# STM32.net
KiCad netlist of a schematic drawn in Altium Designer
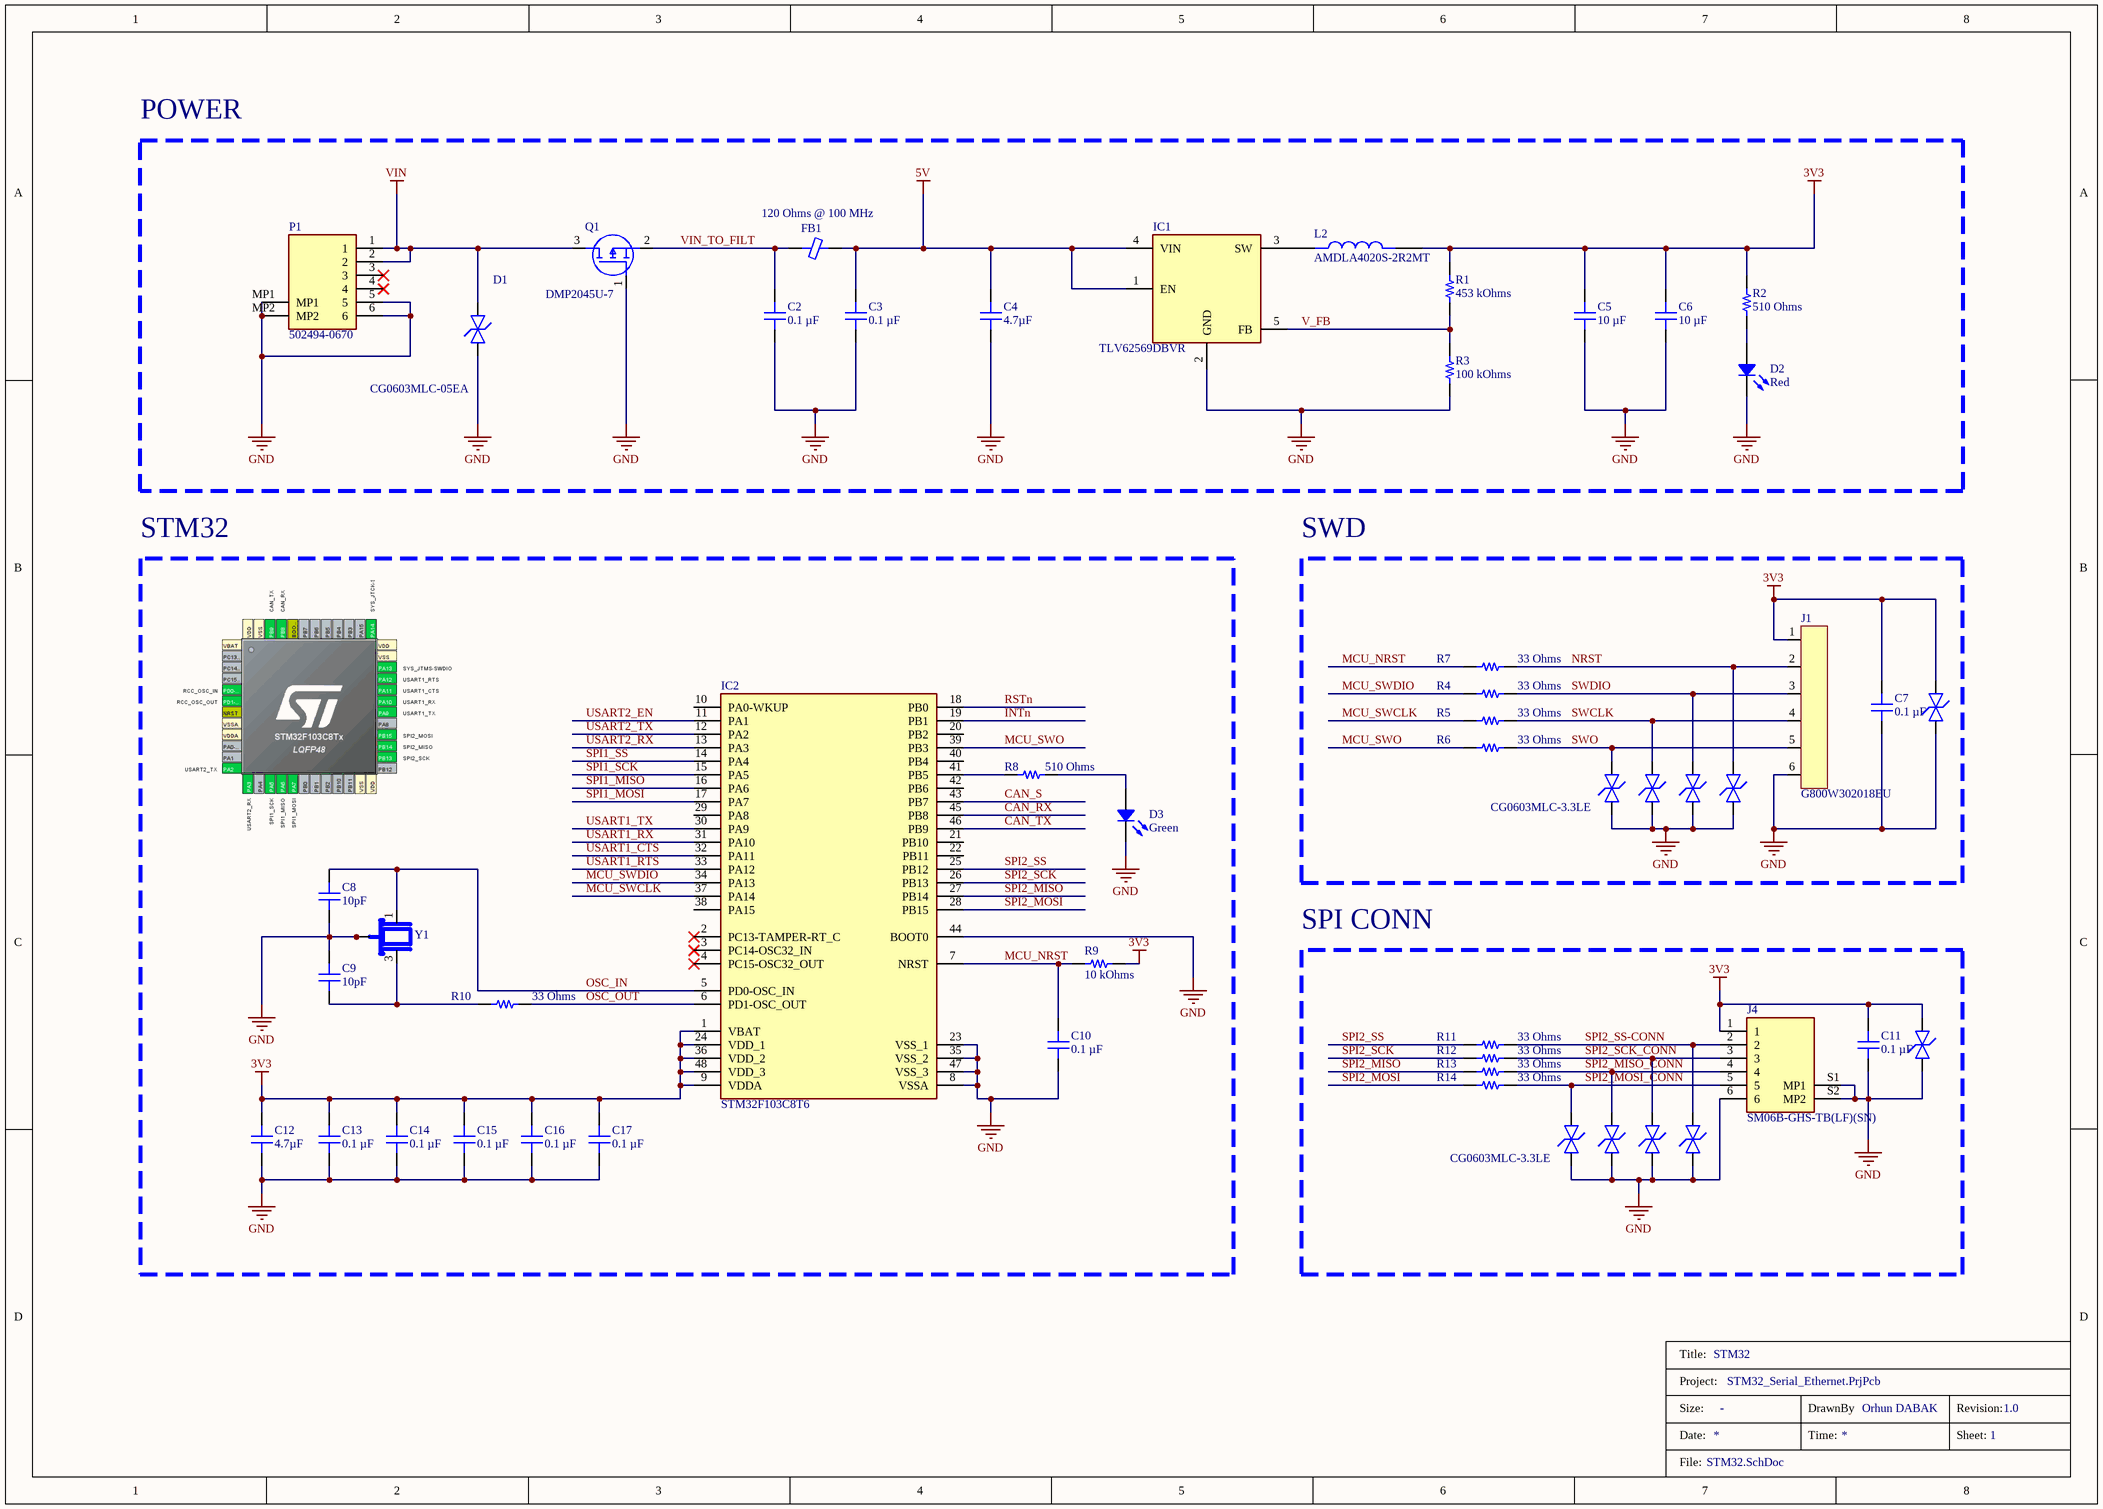
[diagram p0: STM32.SchDoc]

(export (version "E")
  (design (tool "Eeschema 10.0.6"))
  (components
    (comp (ref "C2")
      (value "0.1 µF")
      (footprint "CAP 0603_1608")
      (description "CAP CER 0.1UF 16V X7R 0603")
      (fields (field (name "PART NUMBER") "CS0603KRX7R7BB104") (field (name "MANUFACTURER") "Yageo"))
      (libsource (lib "Celestial Altium Library - altium_library") (part "Capacitor"))
    )
    (comp (ref "C3")
      (value "0.1 µF")
      (footprint "CAP 0603_1608")
      (description "CAP CER 0.1UF 16V X7R 0603")
      (fields (field (name "PART NUMBER") "CS0603KRX7R7BB104") (field (name "MANUFACTURER") "Yageo"))
      (libsource (lib "Celestial Altium Library - altium_library") (part "Capacitor"))
    )
    (comp (ref "C4")
      (value "4.7µF")
      (footprint "CAP 0805_2012")
      (description "CAP CER 4.7UF 16V X7R 0805")
      (fields (field (name "PART NUMBER") "0805YC475MAT2A") (field (name "MANUFACTURER") "AVX Corporation"))
      (libsource (lib "Celestial Altium Library - altium_library") (part "Capacitor"))
    )
    (comp (ref "C5")
      (value "10 µF")
      (footprint "CAP 0805_2012")
      (description "CAP CER 10UF 16V X6S 0805")
      (fields
        (field (name "PART NUMBER") "C2012X6S1C106K125AC")
        (field (name "MANUFACTURER") "TDK Corporation")
      )
      (libsource (lib "Celestial Altium Library - altium_library") (part "Capacitor"))
    )
    (comp (ref "C6")
      (value "10 µF")
      (footprint "CAP 0805_2012")
      (description "CAP CER 10UF 16V X6S 0805")
      (fields
        (field (name "PART NUMBER") "C2012X6S1C106K125AC")
        (field (name "MANUFACTURER") "TDK Corporation")
      )
      (libsource (lib "Celestial Altium Library - altium_library") (part "Capacitor"))
    )
    (comp (ref "C7")
      (value "0.1 µF")
      (footprint "CAP 0603_1608")
      (description "CAP CER 0.1UF 16V X7R 0603")
      (fields (field (name "PART NUMBER") "CS0603KRX7R7BB104") (field (name "MANUFACTURER") "Yageo"))
      (libsource (lib "Celestial Altium Library - altium_library") (part "Capacitor"))
    )
    (comp (ref "C8")
      (value "10pF")
      (footprint "CAP 0603_1608")
      (description "CAP CER 10PF 50V NP0 0603")
      (fields (field (name "PART NUMBER") "06035A100J4T2A") (field (name "MANUFACTURER") "AVX Corporation"))
      (libsource (lib "Celestial Altium Library - altium_library") (part "Capacitor"))
    )
    (comp (ref "C9")
      (value "10pF")
      (footprint "CAP 0603_1608")
      (description "CAP CER 10PF 50V NP0 0603")
      (fields (field (name "PART NUMBER") "06035A100J4T2A") (field (name "MANUFACTURER") "AVX Corporation"))
      (libsource (lib "Celestial Altium Library - altium_library") (part "Capacitor"))
    )
    (comp (ref "C10")
      (value "0.1 µF")
      (footprint "CAP 0603_1608")
      (description "CAP CER 0.1UF 16V X7R 0603")
      (fields (field (name "PART NUMBER") "CS0603KRX7R7BB104") (field (name "MANUFACTURER") "Yageo"))
      (libsource (lib "Celestial Altium Library - altium_library") (part "Capacitor"))
    )
    (comp (ref "C11")
      (value "0.1 µF")
      (footprint "CAP 0603_1608")
      (description "CAP CER 0.1UF 16V X7R 0603")
      (fields (field (name "PART NUMBER") "CS0603KRX7R7BB104") (field (name "MANUFACTURER") "Yageo"))
      (libsource (lib "Celestial Altium Library - altium_library") (part "Capacitor"))
    )
    (comp (ref "C12")
      (value "4.7µF")
      (footprint "CAP 0805_2012")
      (description "CAP CER 4.7UF 16V X7R 0805")
      (fields (field (name "PART NUMBER") "0805YC475MAT2A") (field (name "MANUFACTURER") "AVX Corporation"))
      (libsource (lib "Celestial Altium Library - altium_library") (part "Capacitor"))
    )
    (comp (ref "C13")
      (value "0.1 µF")
      (footprint "CAP 0603_1608")
      (description "CAP CER 0.1UF 16V X7R 0603")
      (fields (field (name "PART NUMBER") "CS0603KRX7R7BB104") (field (name "MANUFACTURER") "Yageo"))
      (libsource (lib "Celestial Altium Library - altium_library") (part "Capacitor"))
    )
    (comp (ref "C14")
      (value "0.1 µF")
      (footprint "CAP 0603_1608")
      (description "CAP CER 0.1UF 16V X7R 0603")
      (fields (field (name "PART NUMBER") "CS0603KRX7R7BB104") (field (name "MANUFACTURER") "Yageo"))
      (libsource (lib "Celestial Altium Library - altium_library") (part "Capacitor"))
    )
    (comp (ref "C15")
      (value "0.1 µF")
      (footprint "CAP 0603_1608")
      (description "CAP CER 0.1UF 16V X7R 0603")
      (fields (field (name "PART NUMBER") "CS0603KRX7R7BB104") (field (name "MANUFACTURER") "Yageo"))
      (libsource (lib "Celestial Altium Library - altium_library") (part "Capacitor"))
    )
    (comp (ref "C16")
      (value "0.1 µF")
      (footprint "CAP 0603_1608")
      (description "CAP CER 0.1UF 16V X7R 0603")
      (fields (field (name "PART NUMBER") "CS0603KRX7R7BB104") (field (name "MANUFACTURER") "Yageo"))
      (libsource (lib "Celestial Altium Library - altium_library") (part "Capacitor"))
    )
    (comp (ref "C17")
      (value "0.1 µF")
      (footprint "CAP 0603_1608")
      (description "CAP CER 0.1UF 16V X7R 0603")
      (fields (field (name "PART NUMBER") "CS0603KRX7R7BB104") (field (name "MANUFACTURER") "Yageo"))
      (libsource (lib "Celestial Altium Library - altium_library") (part "Capacitor"))
    )
    (comp (ref "D1")
      (value "CG0603MLC-05EA")
      (footprint "SamacSys:DIONC1608X55N")
      (description "TVS Diode (Bi-directional)")
      (libsource (lib "SamacSys") (part "CG0603MLC-05EA"))
    )
    (comp (ref "D2")
      (value "Red")
      (footprint "LED 0603_1608 RED")
      (description "LED RED CLEAR CHIP SMD")
      (fields (field (name "PART NUMBER") "LTST-C193KRKT-2A") (field (name "MANUFACTURER") "Lite-On Inc."))
      (libsource (lib "Celestial Altium Library - altium_library") (part "LED"))
    )
    (comp (ref "D3")
      (value "Green")
      (footprint "LED 0603_1608 GREEN")
      (description "LED SM 0603 3V -/1000/-MCD GREEN")
      (fields
        (field (name "PART NUMBER") "LSM0603453V")
        (field (name "MANUFACTURER") "Visual Communications Company - VCC")
      )
      (libsource (lib "Celestial Altium Library - altium_library") (part "LED"))
    )
    (comp (ref "FB1")
      (value "120 Ohms @ 100 MHz")
      (footprint "FER 0603_1608")
      (description "FERRITE BEAD 120 OHM 0603 1LN")
      (fields (field (name "PART NUMBER") "742792625") (field (name "MANUFACTURER") "Würth Elektronik"))
      (libsource (lib "Celestial Altium Library - altium_library") (part "Ferrite Chip"))
    )
    (comp (ref "IC1")
      (value "TLV62569DBVR")
      (footprint "SamacSys:SOT95P280X145-5N")
      (description "Integrated Circuit")
      (fields (field (name "MOUSER PART NUMBER") "595-TLV62569DBVR"))
      (libsource (lib "SamacSys") (part "TLV62569DBVR"))
    )
    (comp (ref "IC2")
      (value "STM32F103C8T6")
      (footprint "SamacSys:QFP50P900X900X160-48N")
      (description "Integrated Circuit")
      (fields
        (field (name "MANUFACTURER_PART_NUMBER") "stm32f103c8t6")
        (field (name "MOUSER PART NUMBER") "511-STM32F103C8T6")
      )
      (libsource (lib "SamacSys") (part "STM32F103C8T6"))
    )
    (comp (ref "J1")
      (value "G800W302018EU")
      (footprint "G800W302018EU")
      (description "Pin Header 6 Position 2.54mm Pitch")
      (fields (field (name "MANUFACTURER") "Amphenol"))
      (libsource (lib "Schematic-Lib-PhilsLab") (part "G800W302018EU"))
    )
    (comp (ref "J4")
      (value "SM06B-GHS-TB(LF)(SN)")
      (footprint "SnapEDApcb:JST_SM06B-GHS-TB(LF)(SN)")
      (fields (field (name "MP") "SM06B-GHS-TB_LF__SN_") (field (name "MF") "JST Sales"))
      (libsource (lib "SnapEDAsch") (part "SM06B-GHS-TB(LF)(SN)"))
    )
    (comp (ref "L2")
      (value "AMDLA4020S-2R2MT")
      (footprint "IND_AMDLA4020S-2R2MT")
      (description "Power Inductor (SMD), 2.2 uH, Â± 20%, 4.5 A, Shielded, 6 A, 4.4mm x 4mm x 1.8mm")
      (fields (field (name "MF") "Abracon Corporation"))
      (libsource (lib "AMDLA4020S-2R2MT") (part "AMDLA4020S-2R2MT"))
    )
    (comp (ref "P1")
      (value "502494-0670")
      (footprint "MOLEX_502494-0670:MOLEX_502494-0670")
      (description "2.00mm Pitch CLIK-Mateâ„¢ Wire-to-Board PCB Receptacle, Single Row, Right Angle, 6 Circuits")
      (libsource (lib "502494-0670") (part "502494-0670"))
    )
    (comp (ref "Q1")
      (value "DMP2045U-7")
      (footprint "SamacSys:SOT96P240X110-3N")
      (description "MOSFET (P-Channel)")
      (fields (field (name "MOUSER PART NUMBER") "621-DMP2045U-7"))
      (libsource (lib "SamacSys") (part "DMP2045U-7"))
    )
    (comp (ref "R1")
      (value "453 kOhms")
      (footprint "RES 0603_1608")
      (description "RES SMD 453 KOHM 1% 0.3W 0603")
      (fields (field (name "PART NUMBER") "SDR03EZPF4533") (field (name "MANUFACTURER") "Rohm Semiconductor"))
      (libsource (lib "Celestial Altium Library - altium_library") (part "Resistor"))
    )
    (comp (ref "R2")
      (value "510 Ohms")
      (footprint "RES 0603_1608")
      (description "RES 510 OHM 5% 1/10W 0603")
      (fields
        (field (name "PART NUMBER") "RMCF0603JT510R")
        (field (name "MANUFACTURER") "Stackpole Electronics Inc")
      )
      (libsource (lib "Celestial Altium Library - altium_library") (part "Resistor"))
    )
    (comp (ref "R3")
      (value "100 kOhms")
      (footprint "RES 0603_1608")
      (description "RES SMD 100K OHM 1% 1/10W 0603")
      (fields (field (name "PART NUMBER") "RT0603FRE07100KL") (field (name "MANUFACTURER") "Yageo"))
      (libsource (lib "Celestial Altium Library - altium_library") (part "Resistor"))
    )
    (comp (ref "R4")
      (value "33 Ohms")
      (footprint "RES 0603_1608")
      (description "RES 33 OHM 5% 1/10W 0603")
      (fields
        (field (name "PART NUMBER") "RMCF0603JT33R0")
        (field (name "MANUFACTURER") "Stackpole Electronics Inc")
      )
      (libsource (lib "Celestial Altium Library - altium_library") (part "Resistor"))
    )
    (comp (ref "R5")
      (value "33 Ohms")
      (footprint "RES 0603_1608")
      (description "RES 33 OHM 5% 1/10W 0603")
      (fields
        (field (name "PART NUMBER") "RMCF0603JT33R0")
        (field (name "MANUFACTURER") "Stackpole Electronics Inc")
      )
      (libsource (lib "Celestial Altium Library - altium_library") (part "Resistor"))
    )
    (comp (ref "R6")
      (value "33 Ohms")
      (footprint "RES 0603_1608")
      (description "RES 33 OHM 5% 1/10W 0603")
      (fields
        (field (name "PART NUMBER") "RMCF0603JT33R0")
        (field (name "MANUFACTURER") "Stackpole Electronics Inc")
      )
      (libsource (lib "Celestial Altium Library - altium_library") (part "Resistor"))
    )
    (comp (ref "R7")
      (value "33 Ohms")
      (footprint "RES 0603_1608")
      (description "RES 33 OHM 5% 1/10W 0603")
      (fields
        (field (name "PART NUMBER") "RMCF0603JT33R0")
        (field (name "MANUFACTURER") "Stackpole Electronics Inc")
      )
      (libsource (lib "Celestial Altium Library - altium_library") (part "Resistor"))
    )
    (comp (ref "R8")
      (value "510 Ohms")
      (footprint "RES 0603_1608")
      (description "RES 510 OHM 5% 1/10W 0603")
      (fields
        (field (name "PART NUMBER") "RMCF0603JT510R")
        (field (name "MANUFACTURER") "Stackpole Electronics Inc")
      )
      (libsource (lib "Celestial Altium Library - altium_library") (part "Resistor"))
    )
    (comp (ref "R9")
      (value "10 kOhms")
      (footprint "RES 0603_1608")
      (description "RES SMD 10K OHM 5% 1/10W 0603")
      (fields (field (name "PART NUMBER") "CRCW060310K0JNEA") (field (name "MANUFACTURER") "Vishay Dale"))
      (libsource (lib "Celestial Altium Library - altium_library") (part "Resistor"))
    )
    (comp (ref "R10")
      (value "33 Ohms")
      (footprint "RES 0603_1608")
      (description "RES 33 OHM 5% 1/10W 0603")
      (fields
        (field (name "PART NUMBER") "RMCF0603JT33R0")
        (field (name "MANUFACTURER") "Stackpole Electronics Inc")
      )
      (libsource (lib "Celestial Altium Library - altium_library") (part "Resistor"))
    )
    (comp (ref "R11")
      (value "33 Ohms")
      (footprint "RES 0603_1608")
      (description "RES 33 OHM 5% 1/10W 0603")
      (fields
        (field (name "PART NUMBER") "RMCF0603JT33R0")
        (field (name "MANUFACTURER") "Stackpole Electronics Inc")
      )
      (libsource (lib "Celestial Altium Library - altium_library") (part "Resistor"))
    )
    (comp (ref "R12")
      (value "33 Ohms")
      (footprint "RES 0603_1608")
      (description "RES 33 OHM 5% 1/10W 0603")
      (fields
        (field (name "PART NUMBER") "RMCF0603JT33R0")
        (field (name "MANUFACTURER") "Stackpole Electronics Inc")
      )
      (libsource (lib "Celestial Altium Library - altium_library") (part "Resistor"))
    )
    (comp (ref "R13")
      (value "33 Ohms")
      (footprint "RES 0603_1608")
      (description "RES 33 OHM 5% 1/10W 0603")
      (fields
        (field (name "PART NUMBER") "RMCF0603JT33R0")
        (field (name "MANUFACTURER") "Stackpole Electronics Inc")
      )
      (libsource (lib "Celestial Altium Library - altium_library") (part "Resistor"))
    )
    (comp (ref "R14")
      (value "33 Ohms")
      (footprint "RES 0603_1608")
      (description "RES 33 OHM 5% 1/10W 0603")
      (fields
        (field (name "PART NUMBER") "RMCF0603JT33R0")
        (field (name "MANUFACTURER") "Stackpole Electronics Inc")
      )
      (libsource (lib "Celestial Altium Library - altium_library") (part "Resistor"))
    )
    (comp (ref "RV1")
      (value "CG0603MLC-3.3LE")
      (footprint "SamacSys:VARC1608X55N")
      (description "Varistor")
      (fields (field (name "MOUSER PART NUMBER") "652-CG0603MLC-3.3LE"))
      (libsource (lib "SamacSys") (part "CG0603MLC-3.3LE"))
    )
    (comp (ref "RV2")
      (value "CG0603MLC-3.3LE")
      (footprint "SamacSys:VARC1608X55N")
      (description "Varistor")
      (fields (field (name "MOUSER PART NUMBER") "652-CG0603MLC-3.3LE"))
      (libsource (lib "SamacSys") (part "CG0603MLC-3.3LE"))
    )
    (comp (ref "RV3")
      (value "CG0603MLC-3.3LE")
      (footprint "SamacSys:VARC1608X55N")
      (description "Varistor")
      (fields (field (name "MOUSER PART NUMBER") "652-CG0603MLC-3.3LE"))
      (libsource (lib "SamacSys") (part "CG0603MLC-3.3LE"))
    )
    (comp (ref "RV4")
      (value "CG0603MLC-3.3LE")
      (footprint "SamacSys:VARC1608X55N")
      (description "Varistor")
      (fields (field (name "MOUSER PART NUMBER") "652-CG0603MLC-3.3LE"))
      (libsource (lib "SamacSys") (part "CG0603MLC-3.3LE"))
    )
    (comp (ref "RV5")
      (value "CG0603MLC-3.3LE")
      (footprint "SamacSys:VARC1608X55N")
      (description "Varistor")
      (fields (field (name "MOUSER PART NUMBER") "652-CG0603MLC-3.3LE"))
      (libsource (lib "SamacSys") (part "CG0603MLC-3.3LE"))
    )
    (comp (ref "RV6")
      (value "CG0603MLC-3.3LE")
      (footprint "SamacSys:VARC1608X55N")
      (description "Varistor")
      (fields (field (name "MOUSER PART NUMBER") "652-CG0603MLC-3.3LE"))
      (libsource (lib "SamacSys") (part "CG0603MLC-3.3LE"))
    )
    (comp (ref "RV7")
      (value "CG0603MLC-3.3LE")
      (footprint "SamacSys:VARC1608X55N")
      (description "Varistor")
      (fields (field (name "MOUSER PART NUMBER") "652-CG0603MLC-3.3LE"))
      (libsource (lib "SamacSys") (part "CG0603MLC-3.3LE"))
    )
    (comp (ref "RV8")
      (value "CG0603MLC-3.3LE")
      (footprint "SamacSys:VARC1608X55N")
      (description "Varistor")
      (fields (field (name "MOUSER PART NUMBER") "652-CG0603MLC-3.3LE"))
      (libsource (lib "SamacSys") (part "CG0603MLC-3.3LE"))
    )
    (comp (ref "RV9")
      (value "CG0603MLC-3.3LE")
      (footprint "SamacSys:VARC1608X55N")
      (description "Varistor")
      (fields (field (name "MOUSER PART NUMBER") "652-CG0603MLC-3.3LE"))
      (libsource (lib "SamacSys") (part "CG0603MLC-3.3LE"))
    )
    (comp (ref "RV10")
      (value "CG0603MLC-3.3LE")
      (footprint "SamacSys:VARC1608X55N")
      (description "Varistor")
      (fields (field (name "MOUSER PART NUMBER") "652-CG0603MLC-3.3LE"))
      (libsource (lib "SamacSys") (part "CG0603MLC-3.3LE"))
    )
    (comp (ref "Y1")
      (value "X322516MLB4SI")
      (footprint "SamacSys:X322516MLB4SI")
      (description "Crystal or Oscillator")
      (libsource (lib "SamacSys") (part "X322516MLB4SI"))
    )
  )
  (nets
    (net (code "1") (name "/CAN_RX") (class "Default")
      (node (ref "IC2") (pin "45") (pinfunction "PB8_45") (pintype "passive"))
    )
    (net (code "2") (name "/CAN_S") (class "Default")
      (node (ref "IC2") (pin "43") (pinfunction "PB7_43") (pintype "passive"))
    )
    (net (code "3") (name "/CAN_TX") (class "Default")
      (node (ref "IC2") (pin "46") (pinfunction "PB9_46") (pintype "passive"))
    )
    (net (code "4") (name "/INTn") (class "Default")
      (node (ref "IC2") (pin "19") (pinfunction "PB1_19") (pintype "passive"))
    )
    (net (code "5") (name "/MCU_NRST") (class "Default")
      (node (ref "C10") (pin "1") (pinfunction "1_1") (pintype "passive"))
      (node (ref "IC2") (pin "7") (pinfunction "NRST_7") (pintype "passive"))
      (node (ref "R7") (pin "1") (pinfunction "1_1") (pintype "passive"))
      (node (ref "R9") (pin "2") (pinfunction "2_2") (pintype "passive"))
    )
    (net (code "6") (name "/MCU_SWCLK") (class "Default")
      (node (ref "IC2") (pin "37") (pinfunction "PA14_37") (pintype "passive"))
      (node (ref "R5") (pin "1") (pinfunction "1_1") (pintype "passive"))
    )
    (net (code "7") (name "/MCU_SWDIO") (class "Default")
      (node (ref "IC2") (pin "34") (pinfunction "PA13_34") (pintype "passive"))
      (node (ref "R4") (pin "1") (pinfunction "1_1") (pintype "passive"))
    )
    (net (code "8") (name "/MCU_SWO") (class "Default")
      (node (ref "IC2") (pin "39") (pinfunction "PB3_39") (pintype "passive"))
      (node (ref "R6") (pin "1") (pinfunction "1_1") (pintype "passive"))
    )
    (net (code "9") (name "/NRST") (class "Default")
      (node (ref "J1") (pin "2") (pinfunction "2_2") (pintype "passive"))
      (node (ref "R7") (pin "2") (pinfunction "2_2") (pintype "passive"))
      (node (ref "RV2") (pin "2") (pinfunction "2_2") (pintype "passive"))
    )
    (net (code "10") (name "/OSC_IN") (class "Default")
      (node (ref "C8") (pin "2") (pinfunction "2_2") (pintype "passive"))
      (node (ref "IC2") (pin "5") (pinfunction "PD0-OSC_IN_5") (pintype "passive"))
      (node (ref "Y1") (pin "1") (pinfunction "1_1") (pintype "passive"))
    )
    (net (code "11") (name "/OSC_OUT") (class "Default")
      (node (ref "IC2") (pin "6") (pinfunction "PD1-OSC_OUT_6") (pintype "passive"))
      (node (ref "R10") (pin "2") (pinfunction "2_2") (pintype "passive"))
    )
    (net (code "12") (name "/RSTn") (class "Default")
      (node (ref "IC2") (pin "18") (pinfunction "PB0_18") (pintype "passive"))
    )
    (net (code "13") (name "/SPI1_MISO") (class "Default")
      (node (ref "IC2") (pin "16") (pinfunction "PA6_16") (pintype "passive"))
    )
    (net (code "14") (name "/SPI1_MOSI") (class "Default")
      (node (ref "IC2") (pin "17") (pinfunction "PA7_17") (pintype "passive"))
    )
    (net (code "15") (name "/SPI1_SCK") (class "Default")
      (node (ref "IC2") (pin "15") (pinfunction "PA5_15") (pintype "passive"))
    )
    (net (code "16") (name "/SPI1_SS") (class "Default")
      (node (ref "IC2") (pin "14") (pinfunction "PA4_14") (pintype "passive"))
    )
    (net (code "17") (name "/SPI2_MISO") (class "Default")
      (node (ref "IC2") (pin "27") (pinfunction "PB14_27") (pintype "passive"))
      (node (ref "R13") (pin "1") (pinfunction "1_1") (pintype "passive"))
    )
    (net (code "18") (name "/SPI2_MISO_CONN") (class "Default")
      (node (ref "J4") (pin "4") (pinfunction "4_4") (pintype "passive"))
      (node (ref "R13") (pin "2") (pinfunction "2_2") (pintype "passive"))
      (node (ref "RV8") (pin "2") (pinfunction "2_2") (pintype "passive"))
    )
    (net (code "19") (name "/SPI2_MOSI") (class "Default")
      (node (ref "IC2") (pin "28") (pinfunction "PB15_28") (pintype "passive"))
      (node (ref "R14") (pin "1") (pinfunction "1_1") (pintype "passive"))
    )
    (net (code "20") (name "/SPI2_MOSI_CONN") (class "Default")
      (node (ref "J4") (pin "5") (pinfunction "5_5") (pintype "passive"))
      (node (ref "R14") (pin "2") (pinfunction "2_2") (pintype "passive"))
      (node (ref "RV7") (pin "2") (pinfunction "2_2") (pintype "passive"))
    )
    (net (code "21") (name "/SPI2_SCK") (class "Default")
      (node (ref "IC2") (pin "26") (pinfunction "PB13_26") (pintype "passive"))
      (node (ref "R12") (pin "1") (pinfunction "1_1") (pintype "passive"))
    )
    (net (code "22") (name "/SPI2_SCK_CONN") (class "Default")
      (node (ref "J4") (pin "3") (pinfunction "3_3") (pintype "passive"))
      (node (ref "R12") (pin "2") (pinfunction "2_2") (pintype "passive"))
      (node (ref "RV9") (pin "2") (pinfunction "2_2") (pintype "passive"))
    )
    (net (code "23") (name "/SPI2_SS") (class "Default")
      (node (ref "IC2") (pin "25") (pinfunction "PB12_25") (pintype "passive"))
      (node (ref "R11") (pin "1") (pinfunction "1_1") (pintype "passive"))
    )
    (net (code "24") (name "/SPI2_SS-CONN") (class "Default")
      (node (ref "J4") (pin "2") (pinfunction "2_2") (pintype "passive"))
      (node (ref "R11") (pin "2") (pinfunction "2_2") (pintype "passive"))
      (node (ref "RV10") (pin "2") (pinfunction "2_2") (pintype "passive"))
    )
    (net (code "25") (name "/SWCLK") (class "Default")
      (node (ref "J1") (pin "4") (pinfunction "4_4") (pintype "passive"))
      (node (ref "R5") (pin "2") (pinfunction "2_2") (pintype "passive"))
      (node (ref "RV4") (pin "2") (pinfunction "2_2") (pintype "passive"))
    )
    (net (code "26") (name "/SWDIO") (class "Default")
      (node (ref "J1") (pin "3") (pinfunction "3_3") (pintype "passive"))
      (node (ref "R4") (pin "2") (pinfunction "2_2") (pintype "passive"))
      (node (ref "RV5") (pin "2") (pinfunction "2_2") (pintype "passive"))
    )
    (net (code "27") (name "/SWO") (class "Default")
      (node (ref "J1") (pin "5") (pinfunction "5_5") (pintype "passive"))
      (node (ref "R6") (pin "2") (pinfunction "2_2") (pintype "passive"))
      (node (ref "RV3") (pin "2") (pinfunction "2_2") (pintype "passive"))
    )
    (net (code "28") (name "/USART1_CTS") (class "Default")
      (node (ref "IC2") (pin "32") (pinfunction "PA11_32") (pintype "passive"))
    )
    (net (code "29") (name "/USART1_RTS") (class "Default")
      (node (ref "IC2") (pin "33") (pinfunction "PA12_33") (pintype "passive"))
    )
    (net (code "30") (name "/USART1_RX") (class "Default")
      (node (ref "IC2") (pin "31") (pinfunction "PA10_31") (pintype "passive"))
    )
    (net (code "31") (name "/USART1_TX") (class "Default")
      (node (ref "IC2") (pin "30") (pinfunction "PA9_30") (pintype "passive"))
    )
    (net (code "32") (name "/USART2_EN") (class "Default")
      (node (ref "IC2") (pin "11") (pinfunction "PA1_11") (pintype "passive"))
    )
    (net (code "33") (name "/USART2_RX") (class "Default")
      (node (ref "IC2") (pin "13") (pinfunction "PA3_13") (pintype "passive"))
    )
    (net (code "34") (name "/USART2_TX") (class "Default")
      (node (ref "IC2") (pin "12") (pinfunction "PA2_12") (pintype "passive"))
    )
    (net (code "35") (name "/VIN_TO_FILT") (class "Default")
      (node (ref "C2") (pin "2") (pinfunction "2_2") (pintype "passive"))
      (node (ref "FB1") (pin "1") (pinfunction "1_1") (pintype "passive"))
      (node (ref "Q1") (pin "2") (pinfunction "S_2") (pintype "passive"))
    )
    (net (code "36") (name "/V_FB") (class "Default")
      (node (ref "IC1") (pin "5") (pinfunction "FB_5") (pintype "passive"))
      (node (ref "R1") (pin "1") (pinfunction "1_1") (pintype "passive"))
      (node (ref "R3") (pin "1") (pinfunction "1_1") (pintype "passive"))
    )
    (net (code "37") (name "3V3") (class "Default")
      (node (ref "C11") (pin "2") (pinfunction "2_2") (pintype "passive"))
      (node (ref "C12") (pin "2") (pinfunction "2_2") (pintype "passive"))
      (node (ref "C13") (pin "1") (pinfunction "1_1") (pintype "passive"))
      (node (ref "C14") (pin "1") (pinfunction "1_1") (pintype "passive"))
      (node (ref "C15") (pin "1") (pinfunction "1_1") (pintype "passive"))
      (node (ref "C16") (pin "1") (pinfunction "1_1") (pintype "passive"))
      (node (ref "C17") (pin "1") (pinfunction "1_1") (pintype "passive"))
      (node (ref "C5") (pin "2") (pinfunction "2_2") (pintype "passive"))
      (node (ref "C6") (pin "2") (pinfunction "2_2") (pintype "passive"))
      (node (ref "C7") (pin "1") (pinfunction "1_1") (pintype "passive"))
      (node (ref "IC2") (pin "1") (pinfunction "VBAT_1") (pintype "passive"))
      (node (ref "IC2") (pin "24") (pinfunction "VDD_1_24") (pintype "passive"))
      (node (ref "IC2") (pin "36") (pinfunction "VDD_2_36") (pintype "passive"))
      (node (ref "IC2") (pin "48") (pinfunction "VDD_3_48") (pintype "passive"))
      (node (ref "IC2") (pin "9") (pinfunction "VDDA_9") (pintype "passive"))
      (node (ref "J1") (pin "1") (pinfunction "1_1") (pintype "passive"))
      (node (ref "J4") (pin "1") (pinfunction "1_1") (pintype "passive"))
      (node (ref "L2") (pin "2") (pinfunction "2_2") (pintype "passive"))
      (node (ref "R1") (pin "2") (pinfunction "2_2") (pintype "passive"))
      (node (ref "R2") (pin "2") (pinfunction "2_2") (pintype "passive"))
      (node (ref "R9") (pin "1") (pinfunction "1_1") (pintype "passive"))
      (node (ref "RV1") (pin "2") (pinfunction "2_2") (pintype "passive"))
      (node (ref "RV6") (pin "2") (pinfunction "2_2") (pintype "passive"))
    )
    (net (code "38") (name "5V") (class "Default")
      (node (ref "C3") (pin "2") (pinfunction "2_2") (pintype "passive"))
      (node (ref "C4") (pin "2") (pinfunction "2_2") (pintype "passive"))
      (node (ref "FB1") (pin "2") (pinfunction "2_2") (pintype "passive"))
      (node (ref "IC1") (pin "1") (pinfunction "EN_1") (pintype "passive"))
      (node (ref "IC1") (pin "4") (pinfunction "VIN_4") (pintype "passive"))
    )
    (net (code "39") (name "GND") (class "Default")
      (node (ref "C10") (pin "2") (pinfunction "2_2") (pintype "passive"))
      (node (ref "C11") (pin "1") (pinfunction "1_1") (pintype "passive"))
      (node (ref "C12") (pin "1") (pinfunction "1_1") (pintype "passive"))
      (node (ref "C13") (pin "2") (pinfunction "2_2") (pintype "passive"))
      (node (ref "C14") (pin "2") (pinfunction "2_2") (pintype "passive"))
      (node (ref "C15") (pin "2") (pinfunction "2_2") (pintype "passive"))
      (node (ref "C16") (pin "2") (pinfunction "2_2") (pintype "passive"))
      (node (ref "C17") (pin "2") (pinfunction "2_2") (pintype "passive"))
      (node (ref "C2") (pin "1") (pinfunction "1_1") (pintype "passive"))
      (node (ref "C3") (pin "1") (pinfunction "1_1") (pintype "passive"))
      (node (ref "C4") (pin "1") (pinfunction "1_1") (pintype "passive"))
      (node (ref "C5") (pin "1") (pinfunction "1_1") (pintype "passive"))
      (node (ref "C6") (pin "1") (pinfunction "1_1") (pintype "passive"))
      (node (ref "C7") (pin "2") (pinfunction "2_2") (pintype "passive"))
      (node (ref "C8") (pin "1") (pinfunction "1_1") (pintype "passive"))
      (node (ref "C9") (pin "1") (pinfunction "1_1") (pintype "passive"))
      (node (ref "D1") (pin "1") (pinfunction "1_1") (pintype "passive"))
      (node (ref "D2") (pin "2") (pinfunction "2_2") (pintype "passive"))
      (node (ref "D3") (pin "2") (pinfunction "2_2") (pintype "passive"))
      (node (ref "IC1") (pin "2") (pinfunction "GND_2") (pintype "passive"))
      (node (ref "IC2") (pin "23") (pinfunction "VSS_1_23") (pintype "passive"))
      (node (ref "IC2") (pin "35") (pinfunction "VSS_2_35") (pintype "passive"))
      (node (ref "IC2") (pin "44") (pinfunction "BOOT0_44") (pintype "passive"))
      (node (ref "IC2") (pin "47") (pinfunction "VSS_3_47") (pintype "passive"))
      (node (ref "IC2") (pin "8") (pinfunction "VSSA_8") (pintype "passive"))
      (node (ref "J1") (pin "6") (pinfunction "6_6") (pintype "passive"))
      (node (ref "J4") (pin "6") (pinfunction "6_6") (pintype "passive"))
      (node (ref "J4") (pin "S1") (pinfunction "MP1_S1") (pintype "passive"))
      (node (ref "J4") (pin "S2") (pinfunction "MP2_S2") (pintype "passive"))
      (node (ref "P1") (pin "5") (pinfunction "5_5") (pintype "passive"))
      (node (ref "P1") (pin "6") (pinfunction "6_6") (pintype "passive"))
      (node (ref "P1") (pin "MP1") (pinfunction "MP1_MP1") (pintype "passive"))
      (node (ref "P1") (pin "MP2") (pinfunction "MP2_MP2") (pintype "passive"))
      (node (ref "Q1") (pin "1") (pinfunction "G_1") (pintype "passive"))
      (node (ref "R3") (pin "2") (pinfunction "2_2") (pintype "passive"))
      (node (ref "RV1") (pin "1") (pinfunction "1_1") (pintype "passive"))
      (node (ref "RV10") (pin "1") (pinfunction "1_1") (pintype "passive"))
      (node (ref "RV2") (pin "1") (pinfunction "1_1") (pintype "passive"))
      (node (ref "RV3") (pin "1") (pinfunction "1_1") (pintype "passive"))
      (node (ref "RV4") (pin "1") (pinfunction "1_1") (pintype "passive"))
      (node (ref "RV5") (pin "1") (pinfunction "1_1") (pintype "passive"))
      (node (ref "RV6") (pin "1") (pinfunction "1_1") (pintype "passive"))
      (node (ref "RV7") (pin "1") (pinfunction "1_1") (pintype "passive"))
      (node (ref "RV8") (pin "1") (pinfunction "1_1") (pintype "passive"))
      (node (ref "RV9") (pin "1") (pinfunction "1_1") (pintype "passive"))
      (node (ref "Y1") (pin "2") (pinfunction "GND_2") (pintype "power_in"))
      (node (ref "Y1") (pin "4") (pinfunction "GND_4") (pintype "power_in"))
    )
    (net (code "40") (name "Net-(C9-Pad2)") (class "Default")
      (node (ref "C9") (pin "2") (pinfunction "2_2") (pintype "passive"))
      (node (ref "R10") (pin "1") (pinfunction "1_1") (pintype "passive"))
      (node (ref "Y1") (pin "3") (pinfunction "3_3") (pintype "passive"))
    )
    (net (code "41") (name "Net-(D2-Pad1)") (class "Default")
      (node (ref "D2") (pin "1") (pinfunction "1_1") (pintype "passive"))
      (node (ref "R2") (pin "1") (pinfunction "1_1") (pintype "passive"))
    )
    (net (code "42") (name "Net-(D3-Pad1)") (class "Default")
      (node (ref "D3") (pin "1") (pinfunction "1_1") (pintype "passive"))
      (node (ref "R8") (pin "1") (pinfunction "1_1") (pintype "passive"))
    )
    (net (code "43") (name "Net-(IC1-SW)") (class "Default")
      (node (ref "IC1") (pin "3") (pinfunction "SW_3") (pintype "passive"))
      (node (ref "L2") (pin "1") (pinfunction "1_1") (pintype "passive"))
    )
    (net (code "44") (name "Net-(IC2-PB5)") (class "Default")
      (node (ref "IC2") (pin "41") (pinfunction "PB5_41") (pintype "passive"))
      (node (ref "R8") (pin "2") (pinfunction "2_2") (pintype "passive"))
    )
    (net (code "45") (name "VIN") (class "Default")
      (node (ref "D1") (pin "2") (pinfunction "2_2") (pintype "passive"))
      (node (ref "P1") (pin "1") (pinfunction "1_1") (pintype "passive"))
      (node (ref "P1") (pin "2") (pinfunction "2_2") (pintype "passive"))
      (node (ref "Q1") (pin "3") (pinfunction "D_3") (pintype "passive"))
    )
    (net (code "46") (name "unconnected-(IC2-PA0-WKUP-Pad10)") (class "Default")
      (node (ref "IC2") (pin "10") (pinfunction "PA0-WKUP_10") (pintype "passive"))
    )
    (net (code "47") (name "unconnected-(IC2-PA8-Pad29)") (class "Default")
      (node (ref "IC2") (pin "29") (pinfunction "PA8_29") (pintype "passive"))
    )
    (net (code "48") (name "unconnected-(IC2-PA15-Pad38)") (class "Default")
      (node (ref "IC2") (pin "38") (pinfunction "PA15_38") (pintype "passive"))
    )
    (net (code "49") (name "unconnected-(IC2-PB2-Pad20)") (class "Default")
      (node (ref "IC2") (pin "20") (pinfunction "PB2_20") (pintype "passive"))
    )
    (net (code "50") (name "unconnected-(IC2-PB4-Pad40)") (class "Default")
      (node (ref "IC2") (pin "40") (pinfunction "PB4_40") (pintype "passive"))
    )
    (net (code "51") (name "unconnected-(IC2-PB6-Pad42)") (class "Default")
      (node (ref "IC2") (pin "42") (pinfunction "PB6_42") (pintype "passive"))
    )
    (net (code "52") (name "unconnected-(IC2-PB10-Pad21)") (class "Default")
      (node (ref "IC2") (pin "21") (pinfunction "PB10_21") (pintype "passive"))
    )
    (net (code "53") (name "unconnected-(IC2-PB11-Pad22)") (class "Default")
      (node (ref "IC2") (pin "22") (pinfunction "PB11_22") (pintype "passive"))
    )
    (net (code "54") (name "unconnected-(IC2-PC13-TAMPER-RT_C-Pad2)") (class "Default")
      (node (ref "IC2") (pin "2") (pinfunction "PC13-TAMPER-RT_C_2") (pintype "passive+no_connect"))
    )
    (net (code "55") (name "unconnected-(IC2-PC14-OSC32_IN-Pad3)") (class "Default")
      (node (ref "IC2") (pin "3") (pinfunction "PC14-OSC32_IN_3") (pintype "passive+no_connect"))
    )
    (net (code "56") (name "unconnected-(IC2-PC15-OSC32_OUT-Pad4)") (class "Default")
      (node (ref "IC2") (pin "4") (pinfunction "PC15-OSC32_OUT_4") (pintype "passive+no_connect"))
    )
    (net (code "57") (name "unconnected-(P1-Pad3)") (class "Default")
      (node (ref "P1") (pin "3") (pinfunction "3_3") (pintype "passive+no_connect"))
    )
    (net (code "58") (name "unconnected-(P1-Pad4)") (class "Default")
      (node (ref "P1") (pin "4") (pinfunction "4_4") (pintype "passive+no_connect"))
    )
  )
)
